# rev0.net
KiCad netlist of a schematic drawn in EAGLE
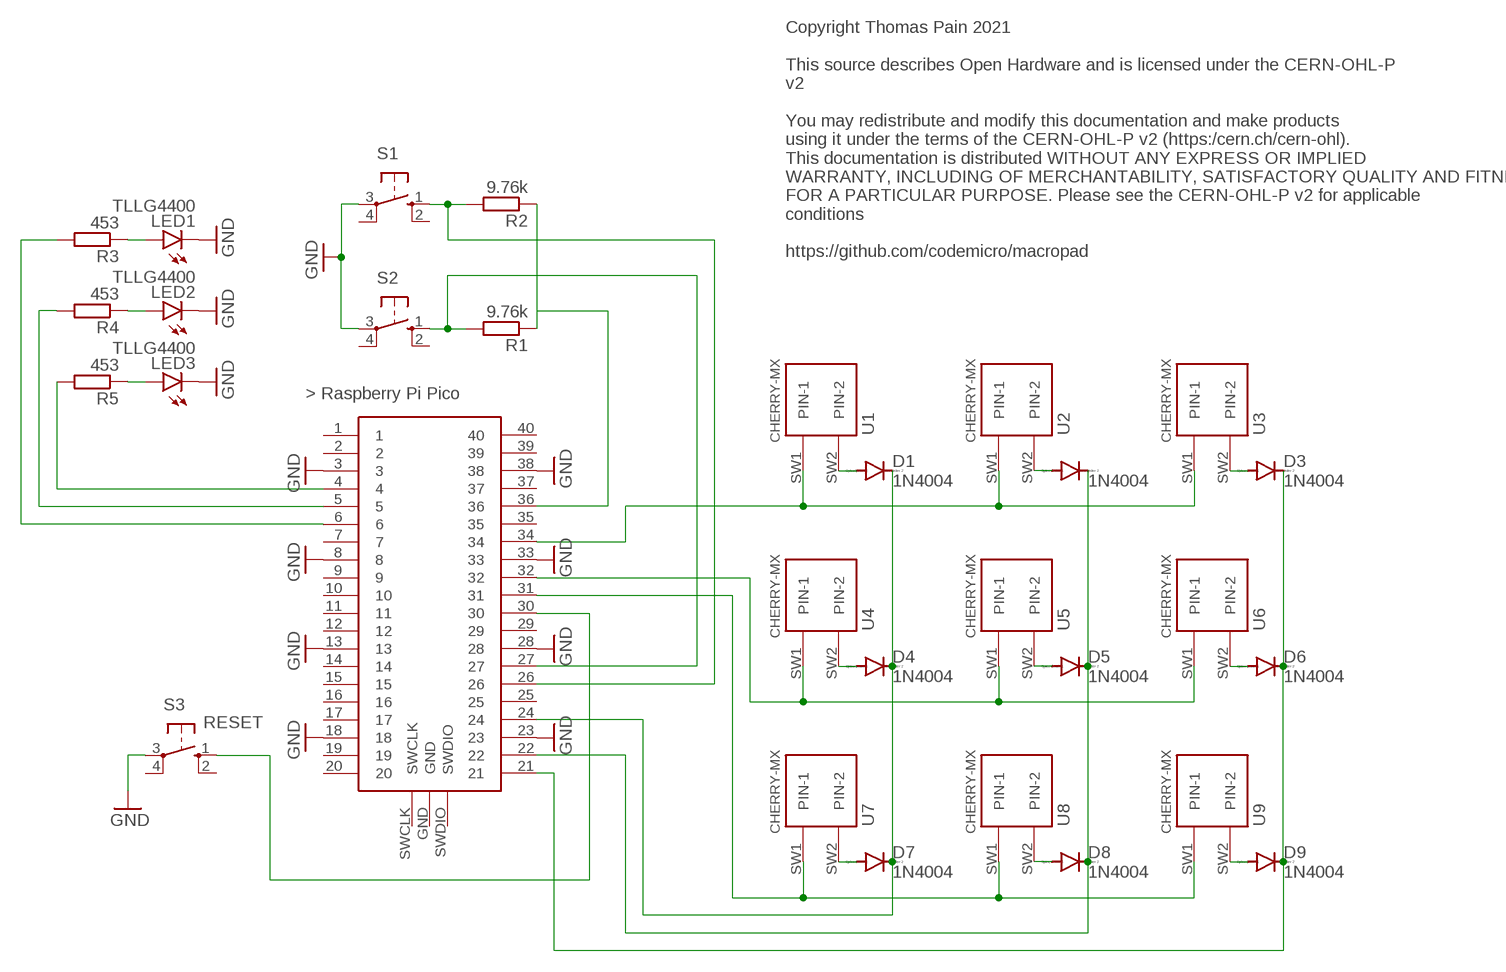
[diagram p0: schematic, sheet 1]

(export (version "E")
  (design (tool "Eeschema 10.0.6"))
  (components
    (comp (ref "D1")
      (value "1N4004")
      (footprint "eagle-import:DO41-10")
      (libsource (lib "eagle-import") (part "1N4004"))
    )
    (comp (ref "D2")
      (value "1N4004")
      (footprint "eagle-import:DO41-10")
      (libsource (lib "eagle-import") (part "1N4004"))
    )
    (comp (ref "D3")
      (value "1N4004")
      (footprint "eagle-import:DO41-10")
      (libsource (lib "eagle-import") (part "1N4004"))
    )
    (comp (ref "D4")
      (value "1N4004")
      (footprint "eagle-import:DO41-10")
      (libsource (lib "eagle-import") (part "1N4004"))
    )
    (comp (ref "D5")
      (value "1N4004")
      (footprint "eagle-import:DO41-10")
      (libsource (lib "eagle-import") (part "1N4004"))
    )
    (comp (ref "D6")
      (value "1N4004")
      (footprint "eagle-import:DO41-10")
      (libsource (lib "eagle-import") (part "1N4004"))
    )
    (comp (ref "D7")
      (value "1N4004")
      (footprint "eagle-import:DO41-10")
      (libsource (lib "eagle-import") (part "1N4004"))
    )
    (comp (ref "D8")
      (value "1N4004")
      (footprint "eagle-import:DO41-10")
      (libsource (lib "eagle-import") (part "1N4004"))
    )
    (comp (ref "D9")
      (value "1N4004")
      (footprint "eagle-import:DO41-10")
      (libsource (lib "eagle-import") (part "1N4004"))
    )
    (comp (ref "LED1")
      (value "TLLG4400")
      (footprint "eagle-import:LED3MM")
      (fields (field (name "MF") "VISHAY SEMICONDUCTOR"))
      (libsource (lib "eagle-import") (part "TLLG4400"))
    )
    (comp (ref "LED2")
      (value "TLLG4400")
      (footprint "eagle-import:LED3MM")
      (fields (field (name "MF") "VISHAY SEMICONDUCTOR"))
      (libsource (lib "eagle-import") (part "TLLG4400"))
    )
    (comp (ref "LED3")
      (value "TLLG4400")
      (footprint "eagle-import:LED3MM")
      (fields (field (name "MF") "VISHAY SEMICONDUCTOR"))
      (libsource (lib "eagle-import") (part "TLLG4400"))
    )
    (comp (ref "R1")
      (value "9.76k")
      (footprint "eagle-import:VMTA55")
      (libsource (lib "eagle-import") (part "R-EU_VMTA55"))
    )
    (comp (ref "R2")
      (value "9.76k")
      (footprint "eagle-import:VMTA55")
      (libsource (lib "eagle-import") (part "R-EU_VMTA55"))
    )
    (comp (ref "R3")
      (value "453")
      (footprint "eagle-import:VMTA55")
      (libsource (lib "eagle-import") (part "R-EU_VMTA55"))
    )
    (comp (ref "R4")
      (value "453")
      (footprint "eagle-import:VMTA55")
      (libsource (lib "eagle-import") (part "R-EU_VMTA55"))
    )
    (comp (ref "R5")
      (value "453")
      (footprint "eagle-import:VMTA55")
      (libsource (lib "eagle-import") (part "R-EU_VMTA55"))
    )
    (comp (ref "S1")
      (value "10-XX")
      (footprint "eagle-import:B3F-10XX")
      (fields (field (name "MPN") "B3F-1000"))
      (libsource (lib "eagle-import") (part "10-XX"))
    )
    (comp (ref "S2")
      (value "10-XX")
      (footprint "eagle-import:B3F-10XX")
      (fields (field (name "MPN") "B3F-1000"))
      (libsource (lib "eagle-import") (part "10-XX"))
    )
    (comp (ref "S3")
      (value "RESET")
      (footprint "eagle-import:B3F-10XX")
      (fields (field (name "MPN") "B3F-1000"))
      (libsource (lib "eagle-import") (part "10-XX"))
    )
    (comp (ref "U$1")
      (value "RASPBERRY-PI-PICO_TH")
      (footprint "eagle-import:FT_RASPBERRY-PI-PICO_TH")
      (libsource (lib "eagle-import") (part "RASPBERRY-PI-PICO_TH"))
    )
    (comp (ref "U1")
      (value "CHERRY-MX")
      (footprint "eagle-import:CHERRY-MX")
      (libsource (lib "eagle-import") (part "CHERRY-MX"))
    )
    (comp (ref "U2")
      (value "CHERRY-MX")
      (footprint "eagle-import:CHERRY-MX")
      (libsource (lib "eagle-import") (part "CHERRY-MX"))
    )
    (comp (ref "U3")
      (value "CHERRY-MX")
      (footprint "eagle-import:CHERRY-MX")
      (libsource (lib "eagle-import") (part "CHERRY-MX"))
    )
    (comp (ref "U4")
      (value "CHERRY-MX")
      (footprint "eagle-import:CHERRY-MX")
      (libsource (lib "eagle-import") (part "CHERRY-MX"))
    )
    (comp (ref "U5")
      (value "CHERRY-MX")
      (footprint "eagle-import:CHERRY-MX")
      (libsource (lib "eagle-import") (part "CHERRY-MX"))
    )
    (comp (ref "U6")
      (value "CHERRY-MX")
      (footprint "eagle-import:CHERRY-MX")
      (libsource (lib "eagle-import") (part "CHERRY-MX"))
    )
    (comp (ref "U7")
      (value "CHERRY-MX")
      (footprint "eagle-import:CHERRY-MX")
      (libsource (lib "eagle-import") (part "CHERRY-MX"))
    )
    (comp (ref "U8")
      (value "CHERRY-MX")
      (footprint "eagle-import:CHERRY-MX")
      (libsource (lib "eagle-import") (part "CHERRY-MX"))
    )
    (comp (ref "U9")
      (value "CHERRY-MX")
      (footprint "eagle-import:CHERRY-MX")
      (libsource (lib "eagle-import") (part "CHERRY-MX"))
    )
  )
  (nets
    (net (code "1") (name "GND") (class "Default")
      (node (ref "LED1") (pin "K") (pinfunction "C_K") (pintype "passive"))
      (node (ref "LED2") (pin "K") (pinfunction "C_K") (pintype "passive"))
      (node (ref "LED3") (pin "K") (pinfunction "C_K") (pintype "passive"))
      (node (ref "S1") (pin "3") (pinfunction "P_3") (pintype "passive"))
      (node (ref "S2") (pin "3") (pinfunction "P_3") (pintype "passive"))
      (node (ref "S3") (pin "3") (pinfunction "P_3") (pintype "passive"))
      (node (ref "U$1") (pin "13") (pinfunction "13_13") (pintype "bidirectional"))
      (node (ref "U$1") (pin "18") (pinfunction "18_18") (pintype "bidirectional"))
      (node (ref "U$1") (pin "23") (pinfunction "23_23") (pintype "bidirectional"))
      (node (ref "U$1") (pin "28") (pinfunction "28_28") (pintype "bidirectional"))
      (node (ref "U$1") (pin "3") (pinfunction "3_3") (pintype "bidirectional"))
      (node (ref "U$1") (pin "33") (pinfunction "33_33") (pintype "bidirectional"))
      (node (ref "U$1") (pin "38") (pinfunction "38_38") (pintype "bidirectional"))
      (node (ref "U$1") (pin "8") (pinfunction "8_8") (pintype "bidirectional"))
    )
    (net (code "2") (name "Net-(D1-PadC)") (class "Default")
      (node (ref "D1") (pin "C") (pinfunction "C_C") (pintype "passive"))
      (node (ref "D4") (pin "C") (pinfunction "C_C") (pintype "passive"))
      (node (ref "D7") (pin "C") (pinfunction "C_C") (pintype "passive"))
      (node (ref "U$1") (pin "24") (pinfunction "24_24") (pintype "bidirectional"))
    )
    (net (code "3") (name "Net-(D2-PadC)") (class "Default")
      (node (ref "D2") (pin "C") (pinfunction "C_C") (pintype "passive"))
      (node (ref "D5") (pin "C") (pinfunction "C_C") (pintype "passive"))
      (node (ref "D8") (pin "C") (pinfunction "C_C") (pintype "passive"))
      (node (ref "U$1") (pin "22") (pinfunction "22_22") (pintype "bidirectional"))
    )
    (net (code "4") (name "Net-(D3-PadC)") (class "Default")
      (node (ref "D3") (pin "C") (pinfunction "C_C") (pintype "passive"))
      (node (ref "D6") (pin "C") (pinfunction "C_C") (pintype "passive"))
      (node (ref "D9") (pin "C") (pinfunction "C_C") (pintype "passive"))
      (node (ref "U$1") (pin "21") (pinfunction "21_21") (pintype "bidirectional"))
    )
    (net (code "5") (name "Net-(LED1-PadA)") (class "Default")
      (node (ref "LED1") (pin "A") (pinfunction "A_A") (pintype "passive"))
      (node (ref "R3") (pin "1") (pinfunction "1_1") (pintype "passive"))
    )
    (net (code "6") (name "Net-(LED2-PadA)") (class "Default")
      (node (ref "LED2") (pin "A") (pinfunction "A_A") (pintype "passive"))
      (node (ref "R4") (pin "1") (pinfunction "1_1") (pintype "passive"))
    )
    (net (code "7") (name "Net-(LED3-PadA)") (class "Default")
      (node (ref "LED3") (pin "A") (pinfunction "A_A") (pintype "passive"))
      (node (ref "R5") (pin "1") (pinfunction "1_1") (pintype "passive"))
    )
    (net (code "8") (name "Net-(R1-Pad1)") (class "Default")
      (node (ref "R1") (pin "1") (pinfunction "1_1") (pintype "passive"))
      (node (ref "R2") (pin "1") (pinfunction "1_1") (pintype "passive"))
      (node (ref "U$1") (pin "36") (pinfunction "36_36") (pintype "bidirectional"))
    )
    (net (code "9") (name "Net-(R3-Pad2)") (class "Default")
      (node (ref "R3") (pin "2") (pinfunction "2_2") (pintype "passive"))
      (node (ref "U$1") (pin "6") (pinfunction "6_6") (pintype "bidirectional"))
    )
    (net (code "10") (name "Net-(R4-Pad2)") (class "Default")
      (node (ref "R4") (pin "2") (pinfunction "2_2") (pintype "passive"))
      (node (ref "U$1") (pin "5") (pinfunction "5_5") (pintype "bidirectional"))
    )
    (net (code "11") (name "Net-(R5-Pad2)") (class "Default")
      (node (ref "R5") (pin "2") (pinfunction "2_2") (pintype "passive"))
      (node (ref "U$1") (pin "4") (pinfunction "4_4") (pintype "bidirectional"))
    )
    (net (code "12") (name "Net-(S1-S)") (class "Default")
      (node (ref "R2") (pin "2") (pinfunction "2_2") (pintype "passive"))
      (node (ref "S1") (pin "1") (pinfunction "S_1") (pintype "passive"))
      (node (ref "U$1") (pin "26") (pinfunction "26_26") (pintype "bidirectional"))
    )
    (net (code "13") (name "Net-(S2-S)") (class "Default")
      (node (ref "R1") (pin "2") (pinfunction "2_2") (pintype "passive"))
      (node (ref "S2") (pin "1") (pinfunction "S_1") (pintype "passive"))
      (node (ref "U$1") (pin "27") (pinfunction "27_27") (pintype "bidirectional"))
    )
    (net (code "14") (name "Net-(S3-S)") (class "Default")
      (node (ref "S3") (pin "1") (pinfunction "S_1") (pintype "passive"))
      (node (ref "U$1") (pin "30") (pinfunction "30_30") (pintype "bidirectional"))
    )
    (net (code "15") (name "Net-(U1-PIN-1)") (class "Default")
      (node (ref "U$1") (pin "34") (pinfunction "34_34") (pintype "bidirectional"))
      (node (ref "U1") (pin "SW1") (pinfunction "PIN-1_SW1") (pintype "bidirectional"))
      (node (ref "U2") (pin "SW1") (pinfunction "PIN-1_SW1") (pintype "bidirectional"))
      (node (ref "U3") (pin "SW1") (pinfunction "PIN-1_SW1") (pintype "bidirectional"))
    )
    (net (code "16") (name "Net-(U1-PIN-2)") (class "Default")
      (node (ref "D1") (pin "A") (pinfunction "A_A") (pintype "passive"))
      (node (ref "U1") (pin "SW2") (pinfunction "PIN-2_SW2") (pintype "bidirectional"))
    )
    (net (code "17") (name "Net-(U2-PIN-2)") (class "Default")
      (node (ref "D2") (pin "A") (pinfunction "A_A") (pintype "passive"))
      (node (ref "U2") (pin "SW2") (pinfunction "PIN-2_SW2") (pintype "bidirectional"))
    )
    (net (code "18") (name "Net-(U3-PIN-2)") (class "Default")
      (node (ref "D3") (pin "A") (pinfunction "A_A") (pintype "passive"))
      (node (ref "U3") (pin "SW2") (pinfunction "PIN-2_SW2") (pintype "bidirectional"))
    )
    (net (code "19") (name "Net-(U4-PIN-1)") (class "Default")
      (node (ref "U$1") (pin "32") (pinfunction "32_32") (pintype "bidirectional"))
      (node (ref "U4") (pin "SW1") (pinfunction "PIN-1_SW1") (pintype "bidirectional"))
      (node (ref "U5") (pin "SW1") (pinfunction "PIN-1_SW1") (pintype "bidirectional"))
      (node (ref "U6") (pin "SW1") (pinfunction "PIN-1_SW1") (pintype "bidirectional"))
    )
    (net (code "20") (name "Net-(U4-PIN-2)") (class "Default")
      (node (ref "D4") (pin "A") (pinfunction "A_A") (pintype "passive"))
      (node (ref "U4") (pin "SW2") (pinfunction "PIN-2_SW2") (pintype "bidirectional"))
    )
    (net (code "21") (name "Net-(U5-PIN-2)") (class "Default")
      (node (ref "D5") (pin "A") (pinfunction "A_A") (pintype "passive"))
      (node (ref "U5") (pin "SW2") (pinfunction "PIN-2_SW2") (pintype "bidirectional"))
    )
    (net (code "22") (name "Net-(U6-PIN-2)") (class "Default")
      (node (ref "D6") (pin "A") (pinfunction "A_A") (pintype "passive"))
      (node (ref "U6") (pin "SW2") (pinfunction "PIN-2_SW2") (pintype "bidirectional"))
    )
    (net (code "23") (name "Net-(U7-PIN-1)") (class "Default")
      (node (ref "U$1") (pin "31") (pinfunction "31_31") (pintype "bidirectional"))
      (node (ref "U7") (pin "SW1") (pinfunction "PIN-1_SW1") (pintype "bidirectional"))
      (node (ref "U8") (pin "SW1") (pinfunction "PIN-1_SW1") (pintype "bidirectional"))
      (node (ref "U9") (pin "SW1") (pinfunction "PIN-1_SW1") (pintype "bidirectional"))
    )
    (net (code "24") (name "Net-(U7-PIN-2)") (class "Default")
      (node (ref "D7") (pin "A") (pinfunction "A_A") (pintype "passive"))
      (node (ref "U7") (pin "SW2") (pinfunction "PIN-2_SW2") (pintype "bidirectional"))
    )
    (net (code "25") (name "Net-(U8-PIN-2)") (class "Default")
      (node (ref "D8") (pin "A") (pinfunction "A_A") (pintype "passive"))
      (node (ref "U8") (pin "SW2") (pinfunction "PIN-2_SW2") (pintype "bidirectional"))
    )
    (net (code "26") (name "Net-(U9-PIN-2)") (class "Default")
      (node (ref "D9") (pin "A") (pinfunction "A_A") (pintype "passive"))
      (node (ref "U9") (pin "SW2") (pinfunction "PIN-2_SW2") (pintype "bidirectional"))
    )
    (net (code "27") (name "unconnected-(S1-P1-Pad4)") (class "Default")
      (node (ref "S1") (pin "4") (pinfunction "P1_4") (pintype "passive"))
    )
    (net (code "28") (name "unconnected-(S1-S1-Pad2)") (class "Default")
      (node (ref "S1") (pin "2") (pinfunction "S1_2") (pintype "passive"))
    )
    (net (code "29") (name "unconnected-(S2-P1-Pad4)") (class "Default")
      (node (ref "S2") (pin "4") (pinfunction "P1_4") (pintype "passive"))
    )
    (net (code "30") (name "unconnected-(S2-S1-Pad2)") (class "Default")
      (node (ref "S2") (pin "2") (pinfunction "S1_2") (pintype "passive"))
    )
    (net (code "31") (name "unconnected-(S3-P1-Pad4)") (class "Default")
      (node (ref "S3") (pin "4") (pinfunction "P1_4") (pintype "passive"))
    )
    (net (code "32") (name "unconnected-(S3-S1-Pad2)") (class "Default")
      (node (ref "S3") (pin "2") (pinfunction "S1_2") (pintype "passive"))
    )
    (net (code "33") (name "unconnected-(U$1-Pad1)") (class "Default")
      (node (ref "U$1") (pin "1") (pinfunction "1_1") (pintype "bidirectional"))
    )
    (net (code "34") (name "unconnected-(U$1-Pad2)") (class "Default")
      (node (ref "U$1") (pin "2") (pinfunction "2_2") (pintype "bidirectional"))
    )
    (net (code "35") (name "unconnected-(U$1-Pad7)") (class "Default")
      (node (ref "U$1") (pin "7") (pinfunction "7_7") (pintype "bidirectional"))
    )
    (net (code "36") (name "unconnected-(U$1-Pad9)") (class "Default")
      (node (ref "U$1") (pin "9") (pinfunction "9_9") (pintype "bidirectional"))
    )
    (net (code "37") (name "unconnected-(U$1-Pad10)") (class "Default")
      (node (ref "U$1") (pin "10") (pinfunction "10_10") (pintype "bidirectional"))
    )
    (net (code "38") (name "unconnected-(U$1-Pad11)") (class "Default")
      (node (ref "U$1") (pin "11") (pinfunction "11_11") (pintype "bidirectional"))
    )
    (net (code "39") (name "unconnected-(U$1-Pad12)") (class "Default")
      (node (ref "U$1") (pin "12") (pinfunction "12_12") (pintype "bidirectional"))
    )
    (net (code "40") (name "unconnected-(U$1-Pad14)") (class "Default")
      (node (ref "U$1") (pin "14") (pinfunction "14_14") (pintype "bidirectional"))
    )
    (net (code "41") (name "unconnected-(U$1-Pad15)") (class "Default")
      (node (ref "U$1") (pin "15") (pinfunction "15_15") (pintype "bidirectional"))
    )
    (net (code "42") (name "unconnected-(U$1-Pad16)") (class "Default")
      (node (ref "U$1") (pin "16") (pinfunction "16_16") (pintype "bidirectional"))
    )
    (net (code "43") (name "unconnected-(U$1-Pad17)") (class "Default")
      (node (ref "U$1") (pin "17") (pinfunction "17_17") (pintype "bidirectional"))
    )
    (net (code "44") (name "unconnected-(U$1-Pad19)") (class "Default")
      (node (ref "U$1") (pin "19") (pinfunction "19_19") (pintype "bidirectional"))
    )
    (net (code "45") (name "unconnected-(U$1-Pad20)") (class "Default")
      (node (ref "U$1") (pin "20") (pinfunction "20_20") (pintype "bidirectional"))
    )
    (net (code "46") (name "unconnected-(U$1-Pad25)") (class "Default")
      (node (ref "U$1") (pin "25") (pinfunction "25_25") (pintype "bidirectional"))
    )
    (net (code "47") (name "unconnected-(U$1-Pad29)") (class "Default")
      (node (ref "U$1") (pin "29") (pinfunction "29_29") (pintype "bidirectional"))
    )
    (net (code "48") (name "unconnected-(U$1-Pad35)") (class "Default")
      (node (ref "U$1") (pin "35") (pinfunction "35_35") (pintype "bidirectional"))
    )
    (net (code "49") (name "unconnected-(U$1-Pad37)") (class "Default")
      (node (ref "U$1") (pin "37") (pinfunction "37_37") (pintype "bidirectional"))
    )
    (net (code "50") (name "unconnected-(U$1-Pad39)") (class "Default")
      (node (ref "U$1") (pin "39") (pinfunction "39_39") (pintype "bidirectional"))
    )
    (net (code "51") (name "unconnected-(U$1-Pad40)") (class "Default")
      (node (ref "U$1") (pin "40") (pinfunction "40_40") (pintype "bidirectional"))
    )
    (net (code "52") (name "unconnected-(U$1-PadGND)") (class "Default")
      (node (ref "U$1") (pin "GND") (pinfunction "GND_GND") (pintype "bidirectional"))
    )
    (net (code "53") (name "unconnected-(U$1-PadSWCLK)") (class "Default")
      (node (ref "U$1") (pin "SWCLK") (pinfunction "SWCLK_SWCLK") (pintype "bidirectional"))
    )
    (net (code "54") (name "unconnected-(U$1-PadSWDIO)") (class "Default")
      (node (ref "U$1") (pin "SWDIO") (pinfunction "SWDIO_SWDIO") (pintype "bidirectional"))
    )
  )
)
